# mcu_support.net
KiCad netlist of a schematic drawn in Altium Designer
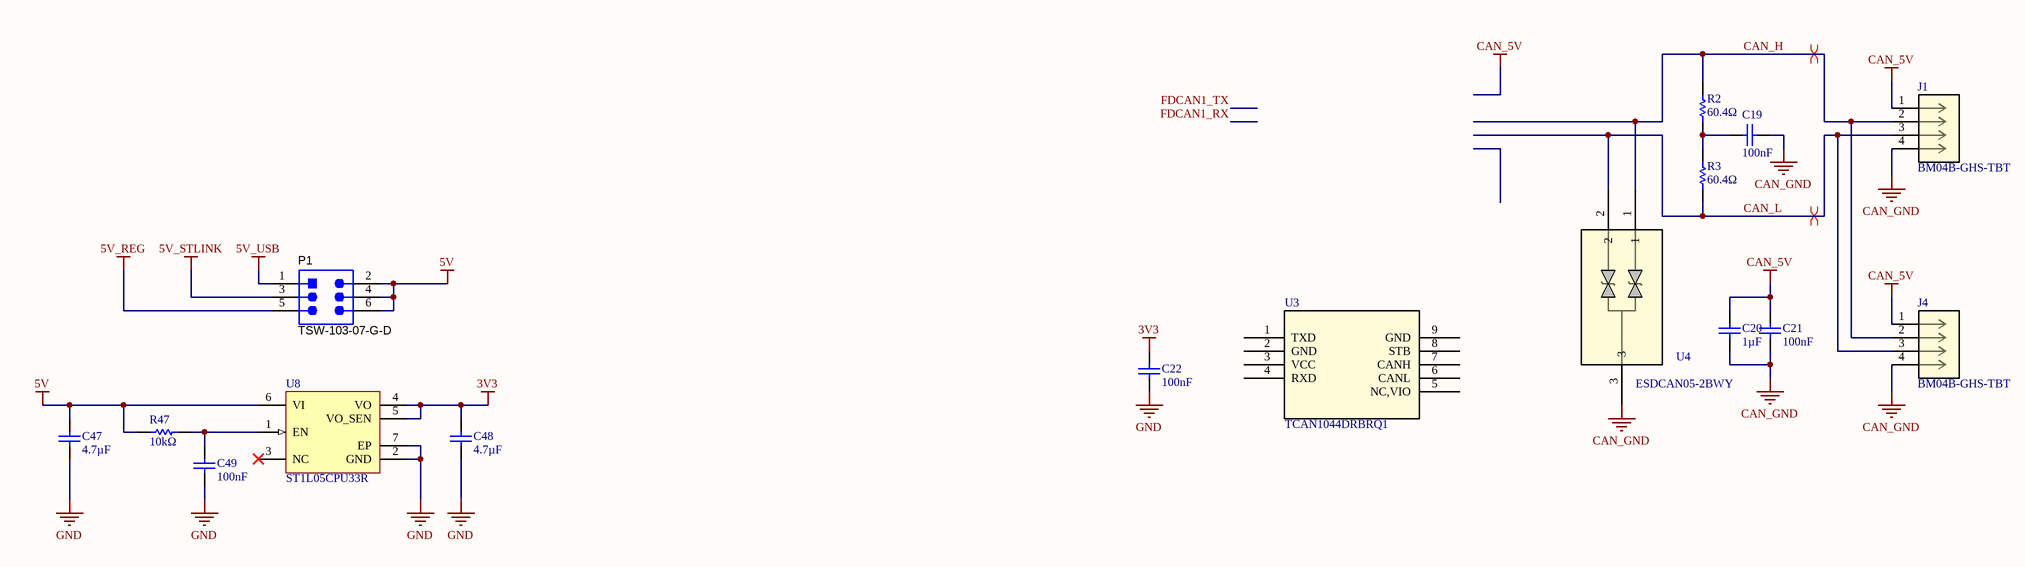
[diagram p0: mcu_support.SchDoc]

(export (version "E")
  (design (tool "Eeschema 10.0.6"))
  (components
    (comp (ref "C19")
      (value "100nF")
      (footprint "C0603")
      (description "25V 100nF X7R ±10% 0603 Multilayer Ceramic Capacitors MLCC - SMD/SMT ROHS")
      (fields (field (name "TOLERANCE") "10%") (field (name "VOLTAGE") "25V"))
      (libsource (lib "Sunswift Racing") (part "Capacitor"))
    )
    (comp (ref "C20")
      (value "1µF")
      (footprint "C0603")
      (description "16V 1uF X7R ±10% 0603 Multilayer Ceramic Capacitors MLCC - SMD/SMT ROHS")
      (fields (field (name "VOLTAGE") "16V") (field (name "TOLERANCE") "10%"))
      (libsource (lib "Sunswift Racing") (part "Capacitor"))
    )
    (comp (ref "C21")
      (value "100nF")
      (footprint "C0603")
      (description "25V 100nF X7R ±10% 0603 Multilayer Ceramic Capacitors MLCC - SMD/SMT ROHS")
      (fields (field (name "TOLERANCE") "10%") (field (name "VOLTAGE") "25V"))
      (libsource (lib "Sunswift Racing") (part "Capacitor"))
    )
    (comp (ref "C22")
      (value "100nF")
      (footprint "C0603")
      (description "25V 100nF X7R ±10% 0603 Multilayer Ceramic Capacitors MLCC - SMD/SMT ROHS")
      (fields (field (name "TOLERANCE") "10%") (field (name "VOLTAGE") "25V"))
      (libsource (lib "Sunswift Racing") (part "Capacitor"))
    )
    (comp (ref "C47")
      (value "4.7µF")
      (footprint "C0603")
      (description "16V 4.7uF X5R ±10% 0603 Multilayer Ceramic Capacitors MLCC - SMD/SMT ROHS")
      (fields (field (name "TOLERANCE") "10%") (field (name "Comment") "CC0603KRX5R7BB475"))
      (libsource (lib "Sunswift Racing") (part "Capacitor"))
    )
    (comp (ref "C48")
      (value "4.7µF")
      (footprint "C0603")
      (description "16V 4.7uF X5R ±10% 0603 Multilayer Ceramic Capacitors MLCC - SMD/SMT ROHS")
      (fields (field (name "TOLERANCE") "10%") (field (name "Comment") "CC0603KRX5R7BB475"))
      (libsource (lib "Sunswift Racing") (part "Capacitor"))
    )
    (comp (ref "C49")
      (value "100nF")
      (footprint "C0603")
      (description "25V 100nF X7R ±10% 0603 Multilayer Ceramic Capacitors MLCC - SMD/SMT ROHS")
      (fields (field (name "TOLERANCE") "10%") (field (name "VOLTAGE") "25V"))
      (libsource (lib "Sunswift Racing") (part "Capacitor"))
    )
    (comp (ref "J1")
      (value "BM04B-GHS-TBT")
      (footprint "CONN_BM04B-GHS-TBT_JST")
      (description "Description")
      (fields (field (name "COPYRIGHT") "Copyright (C) 2026 Ultra Librarian. All rights reserved."))
      (libsource (lib "Sunswift Racing") (part "BM04B-GHS-TBT"))
    )
    (comp (ref "J4")
      (value "BM04B-GHS-TBT")
      (footprint "CONN_BM04B-GHS-TBT_JST")
      (description "Description")
      (fields (field (name "COPYRIGHT") "Copyright (C) 2026 Ultra Librarian. All rights reserved."))
      (libsource (lib "Sunswift Racing") (part "BM04B-GHS-TBT"))
    )
    (comp (ref "P1")
      (value "TSW-103-07-G-D")
      (footprint "SMTC-TSW-103-07-G-D_V")
      (description "CONN HEADER VERT 6POS 2.54MM / Connector Header Through Hole 6 position 0.100\" (2.54mm)")
      (libsource (lib "Sunswift Racing") (part "CN-2P-M-R6"))
    )
    (comp (ref "R2")
      (value "60.4Ω")
      (footprint "RESC1608X55X25ML10T15")
      (description "Res Thick Film 0603 60.4 Ohm 1% 0.1W(1/10W) ±100ppm/C Pad SMD T/R")
      (fields (field (name "TOLERANCE") "1%") (field (name "Comment") "RC0603FR-0760R4L"))
      (libsource (lib "Sunswift Racing") (part "RES-2"))
    )
    (comp (ref "R3")
      (value "60.4Ω")
      (footprint "RESC1608X55X25ML10T15")
      (description "Res Thick Film 0603 60.4 Ohm 1% 0.1W(1/10W) ±100ppm/C Pad SMD T/R")
      (fields (field (name "TOLERANCE") "1%") (field (name "Comment") "RC0603FR-0760R4L"))
      (libsource (lib "Sunswift Racing") (part "RES-2"))
    )
    (comp (ref "R47")
      (value "10kΩ")
      (footprint "RESC1608X55X25ML10T15")
      (description "10 kOhms ±1% 0.1W, 1/10W Chip Resistor 0603 (1608 Metric) Moisture Resistant Thick Film")
      (fields (field (name "TOLERANCE") "1%") (field (name "Comment") "RC0603FR-0710KL"))
      (libsource (lib "Sunswift Racing") (part "RES-2"))
    )
    (comp (ref "U3")
      (value "TCAN1044DRBRQ1")
      (footprint "SON_4DRBRQ1_TEX")
      (description "Automotive high-speed CAN transceiver 8-SON -40 to 125")
      (fields (field (name "COPYRIGHT") "Copyright (C) 2025 Ultra Librarian. All rights reserved."))
      (libsource (lib "Sunswift Racing") (part "TCAN1044DRBRQ1"))
    )
    (comp (ref "U4")
      (value "ESDCAN05-2BWY")
      (footprint "SOT323-3L_STM")
      (description "Automotive dual-line TVS in SOT323-3L for CAN bus (24 V system)")
      (fields (field (name "COPYRIGHT") "Copyright (C) 2025 Ultra Librarian. All rights reserved."))
      (libsource (lib "Sunswift Racing") (part "ESDCAN05-2BWY"))
    )
    (comp (ref "U8")
      (value "ST1L05CPU33R")
      (footprint "DFN6D_L")
      (description "ST1L05 Series 1.3 A 3.3 V Fixed Output LDO BICMOS Voltage Regulator - DFN-6")
      (libsource (lib "Sunswift Racing") (part "PM-REG-ST1L05C-SQ7"))
    )
  )
  (nets
    (net (code "1") (name "/CAN_H") (class "Default")
      (node (ref "J1") (pin "2") (pinfunction "2_2") (pintype "passive"))
      (node (ref "J4") (pin "2") (pinfunction "2_2") (pintype "passive"))
      (node (ref "R2") (pin "2") (pinfunction "2_2") (pintype "passive"))
      (node (ref "U4") (pin "1") (pinfunction "1_1") (pintype "passive"))
    )
    (net (code "2") (name "/CAN_L") (class "Default")
      (node (ref "J1") (pin "3") (pinfunction "3_3") (pintype "passive"))
      (node (ref "J4") (pin "3") (pinfunction "3_3") (pintype "passive"))
      (node (ref "R3") (pin "1") (pinfunction "1_1") (pintype "passive"))
      (node (ref "U4") (pin "2") (pinfunction "2_2") (pintype "passive"))
    )
    (net (code "5") (name "3V3") (class "Default")
      (node (ref "C22") (pin "2") (pinfunction "2_2") (pintype "passive"))
      (node (ref "C48") (pin "2") (pinfunction "2_2") (pintype "passive"))
      (node (ref "U8") (pin "4") (pinfunction "VO_4") (pintype "power_in"))
      (node (ref "U8") (pin "5") (pinfunction "VO_SEN_5") (pintype "passive"))
    )
    (net (code "6") (name "5V") (class "Default")
      (node (ref "C47") (pin "2") (pinfunction "2_2") (pintype "passive"))
      (node (ref "P1") (pin "2") (pinfunction "2_2") (pintype "passive"))
      (node (ref "P1") (pin "4") (pinfunction "4_4") (pintype "passive"))
      (node (ref "P1") (pin "6") (pinfunction "6_6") (pintype "passive"))
      (node (ref "R47") (pin "1") (pinfunction "1_1") (pintype "passive"))
      (node (ref "U8") (pin "6") (pinfunction "VI_6") (pintype "power_in"))
    )
    (net (code "7") (name "5V_REG") (class "Default")
      (node (ref "P1") (pin "5") (pinfunction "5_5") (pintype "passive"))
    )
    (net (code "8") (name "5V_STLINK") (class "Default")
      (node (ref "P1") (pin "3") (pinfunction "3_3") (pintype "passive"))
    )
    (net (code "9") (name "5V_USB") (class "Default")
      (node (ref "P1") (pin "1") (pinfunction "1_1") (pintype "passive"))
    )
    (net (code "10") (name "CAN_5V") (class "Default")
      (node (ref "C20") (pin "2") (pinfunction "2_2") (pintype "passive"))
      (node (ref "C21") (pin "2") (pinfunction "2_2") (pintype "passive"))
      (node (ref "J1") (pin "1") (pinfunction "1_1") (pintype "passive"))
      (node (ref "J4") (pin "1") (pinfunction "1_1") (pintype "passive"))
    )
    (net (code "11") (name "CAN_GND") (class "Default")
      (node (ref "C19") (pin "1") (pinfunction "1_1") (pintype "passive"))
      (node (ref "C20") (pin "1") (pinfunction "1_1") (pintype "passive"))
      (node (ref "C21") (pin "1") (pinfunction "1_1") (pintype "passive"))
      (node (ref "J1") (pin "4") (pinfunction "4_4") (pintype "passive"))
      (node (ref "J4") (pin "4") (pinfunction "4_4") (pintype "passive"))
      (node (ref "U4") (pin "3") (pinfunction "3_3") (pintype "passive"))
    )
    (net (code "12") (name "GND") (class "Default")
      (node (ref "C22") (pin "1") (pinfunction "1_1") (pintype "passive"))
      (node (ref "C47") (pin "1") (pinfunction "1_1") (pintype "passive"))
      (node (ref "C48") (pin "1") (pinfunction "1_1") (pintype "passive"))
      (node (ref "C49") (pin "1") (pinfunction "1_1") (pintype "passive"))
      (node (ref "U8") (pin "2") (pinfunction "GND_2") (pintype "power_in"))
      (node (ref "U8") (pin "7") (pinfunction "EP_7") (pintype "power_in"))
    )
    (net (code "13") (name "Net-(C19-Pad2)") (class "Default")
      (node (ref "C19") (pin "2") (pinfunction "2_2") (pintype "passive"))
      (node (ref "R2") (pin "1") (pinfunction "1_1") (pintype "passive"))
      (node (ref "R3") (pin "2") (pinfunction "2_2") (pintype "passive"))
    )
    (net (code "14") (name "Net-(U8-EN)") (class "Default")
      (node (ref "C49") (pin "2") (pinfunction "2_2") (pintype "passive"))
      (node (ref "R47") (pin "2") (pinfunction "2_2") (pintype "passive"))
      (node (ref "U8") (pin "1") (pinfunction "EN_1") (pintype "input"))
    )
    (net (code "15") (name "unconnected-(U3-CANH-Pad7)") (class "Default")
      (node (ref "U3") (pin "7") (pinfunction "CANH_7") (pintype "passive"))
    )
    (net (code "16") (name "unconnected-(U3-CANL-Pad6)") (class "Default")
      (node (ref "U3") (pin "6") (pinfunction "CANL_6") (pintype "passive"))
    )
    (net (code "17") (name "unconnected-(U3-GND-Pad2)") (class "Default")
      (node (ref "U3") (pin "2") (pinfunction "GND_2") (pintype "power_in"))
    )
    (net (code "18") (name "unconnected-(U3-GND-Pad9)") (class "Default")
      (node (ref "U3") (pin "9") (pinfunction "GND_9") (pintype "power_in"))
    )
    (net (code "19") (name "unconnected-(U3-NC,VIO-Pad5)") (class "Default")
      (node (ref "U3") (pin "5") (pinfunction "NC,VIO_5") (pintype "passive"))
    )
    (net (code "20") (name "unconnected-(U3-RXD-Pad4)") (class "Default")
      (node (ref "U3") (pin "4") (pinfunction "RXD_4") (pintype "passive"))
    )
    (net (code "21") (name "unconnected-(U3-STB-Pad8)") (class "Default")
      (node (ref "U3") (pin "8") (pinfunction "STB_8") (pintype "passive"))
    )
    (net (code "22") (name "unconnected-(U3-TXD-Pad1)") (class "Default")
      (node (ref "U3") (pin "1") (pinfunction "TXD_1") (pintype "passive"))
    )
    (net (code "23") (name "unconnected-(U3-VCC-Pad3)") (class "Default")
      (node (ref "U3") (pin "3") (pinfunction "VCC_3") (pintype "power_in"))
    )
    (net (code "24") (name "unconnected-(U8-NC-Pad3)") (class "Default")
      (node (ref "U8") (pin "3") (pinfunction "NC_3") (pintype "passive+no_connect"))
    )
  )
)
